# thermistory_array_v2.net
KiCad netlist of a schematic drawn in EAGLE
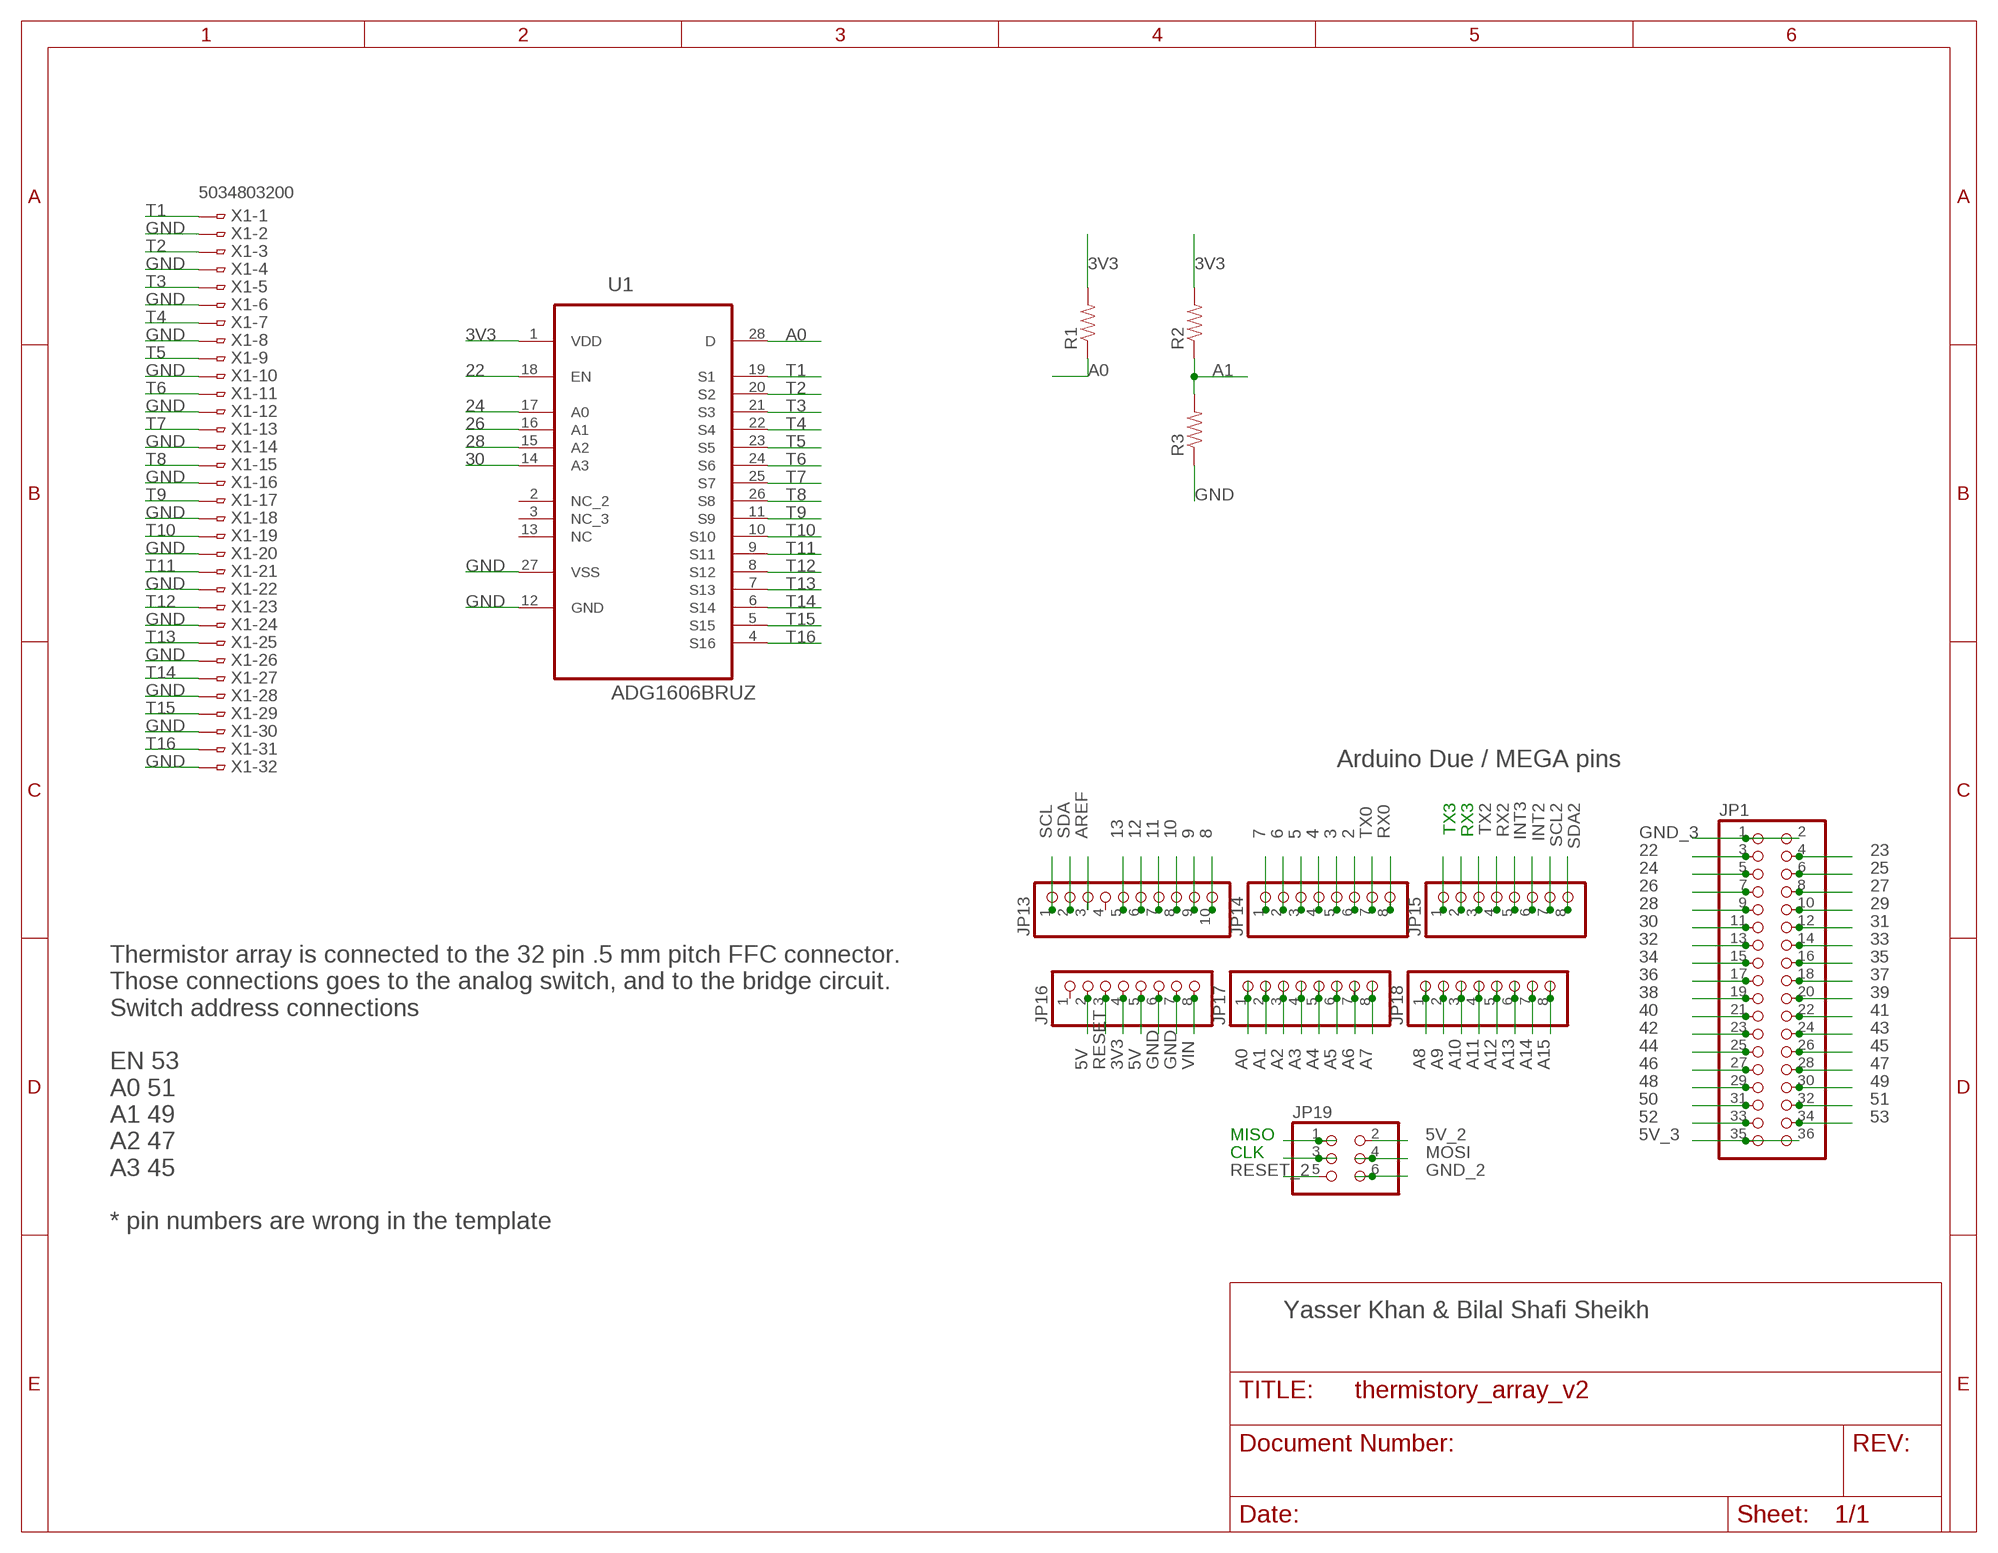
[diagram p0: schematic, sheet 1]

(export (version "E")
  (design (tool "Eeschema 10.0.6"))
  (components
    (comp (ref "JP1")
      (value "PINHD-2X18")
      (footprint "eagle-import:2X18")
      (libsource (lib "eagle-import") (part "PINHD-2X18"))
    )
    (comp (ref "JP13")
      (value "PINHD-1X10")
      (footprint "eagle-import:1X10")
      (libsource (lib "eagle-import") (part "PINHD-1X10"))
    )
    (comp (ref "JP14")
      (value "PINHD-1X8")
      (footprint "eagle-import:1X08")
      (libsource (lib "eagle-import") (part "PINHD-1X8"))
    )
    (comp (ref "JP15")
      (value "PINHD-1X8")
      (footprint "eagle-import:1X08")
      (libsource (lib "eagle-import") (part "PINHD-1X8"))
    )
    (comp (ref "JP16")
      (value "PINHD-1X8")
      (footprint "eagle-import:1X08")
      (libsource (lib "eagle-import") (part "PINHD-1X8"))
    )
    (comp (ref "JP17")
      (value "PINHD-1X8")
      (footprint "eagle-import:1X08")
      (libsource (lib "eagle-import") (part "PINHD-1X8"))
    )
    (comp (ref "JP18")
      (value "PINHD-1X8")
      (footprint "eagle-import:1X08")
      (libsource (lib "eagle-import") (part "PINHD-1X8"))
    )
    (comp (ref "JP19")
      (value "PINHD-2X3")
      (footprint "eagle-import:2X03")
      (libsource (lib "eagle-import") (part "PINHD-2X3"))
    )
    (comp (ref "R1")
      (value "RESISTORKIT")
      (footprint "eagle-import:AXIAL-0.3-KIT")
      (libsource (lib "eagle-import") (part "RESISTORKIT"))
    )
    (comp (ref "R2")
      (value "RESISTORKIT")
      (footprint "eagle-import:AXIAL-0.3-KIT")
      (libsource (lib "eagle-import") (part "RESISTORKIT"))
    )
    (comp (ref "R3")
      (value "RESISTORKIT")
      (footprint "eagle-import:AXIAL-0.3-KIT")
      (libsource (lib "eagle-import") (part "RESISTORKIT"))
    )
    (comp (ref "U1")
      (value "ADG1606BRUZ")
      (footprint "eagle-import:SOP65P640X120-28N")
      (libsource (lib "eagle-import") (part "ADG1606BRUZ"))
    )
    (comp (ref "X1")
      (value "5034803200")
      (footprint "eagle-import:5034803200")
      (libsource (lib "eagle-import") (part "5034803200"))
    )
  )
  (nets
    (net (code "1") (name "/2") (class "Default")
      (node (ref "JP14") (pin "6") (pinfunction "6_6") (pintype "passive"))
    )
    (net (code "2") (name "/3") (class "Default")
      (node (ref "JP14") (pin "5") (pinfunction "5_5") (pintype "passive"))
    )
    (net (code "3") (name "/3V3") (class "Default")
      (node (ref "JP16") (pin "4") (pinfunction "4_4") (pintype "passive"))
      (node (ref "R1") (pin "P$2") (pinfunction "2_P$2") (pintype "passive"))
      (node (ref "R2") (pin "P$2") (pinfunction "2_P$2") (pintype "passive"))
      (node (ref "U1") (pin "1") (pinfunction "VDD_1") (pintype "power_in"))
    )
    (net (code "4") (name "/4") (class "Default")
      (node (ref "JP14") (pin "4") (pinfunction "4_4") (pintype "passive"))
    )
    (net (code "5") (name "/5") (class "Default")
      (node (ref "JP14") (pin "3") (pinfunction "3_3") (pintype "passive"))
    )
    (net (code "6") (name "/5V") (class "Default")
      (node (ref "JP16") (pin "2") (pinfunction "2_2") (pintype "passive"))
      (node (ref "JP16") (pin "5") (pinfunction "5_5") (pintype "passive"))
    )
    (net (code "7") (name "/5V_2") (class "Default")
      (node (ref "JP19") (pin "2") (pinfunction "2_2") (pintype "passive"))
    )
    (net (code "8") (name "/5V_3") (class "Default")
      (node (ref "JP1") (pin "35") (pinfunction "35_35") (pintype "passive"))
      (node (ref "JP1") (pin "36") (pinfunction "36_36") (pintype "passive"))
    )
    (net (code "9") (name "/6") (class "Default")
      (node (ref "JP14") (pin "2") (pinfunction "2_2") (pintype "passive"))
    )
    (net (code "10") (name "/7") (class "Default")
      (node (ref "JP14") (pin "1") (pinfunction "1_1") (pintype "passive"))
    )
    (net (code "11") (name "/8") (class "Default")
      (node (ref "JP13") (pin "10") (pinfunction "10_10") (pintype "passive"))
    )
    (net (code "12") (name "/9") (class "Default")
      (node (ref "JP13") (pin "9") (pinfunction "9_9") (pintype "passive"))
    )
    (net (code "13") (name "/10") (class "Default")
      (node (ref "JP13") (pin "8") (pinfunction "8_8") (pintype "passive"))
    )
    (net (code "14") (name "/11") (class "Default")
      (node (ref "JP13") (pin "7") (pinfunction "7_7") (pintype "passive"))
    )
    (net (code "15") (name "/12") (class "Default")
      (node (ref "JP13") (pin "6") (pinfunction "6_6") (pintype "passive"))
    )
    (net (code "16") (name "/13") (class "Default")
      (node (ref "JP13") (pin "5") (pinfunction "5_5") (pintype "passive"))
    )
    (net (code "17") (name "/22") (class "Default")
      (node (ref "JP1") (pin "3") (pinfunction "3_3") (pintype "passive"))
      (node (ref "U1") (pin "18") (pinfunction "EN_18") (pintype "input"))
    )
    (net (code "18") (name "/23") (class "Default")
      (node (ref "JP1") (pin "4") (pinfunction "4_4") (pintype "passive"))
    )
    (net (code "19") (name "/24") (class "Default")
      (node (ref "JP1") (pin "5") (pinfunction "5_5") (pintype "passive"))
      (node (ref "U1") (pin "17") (pinfunction "A0_17") (pintype "input"))
    )
    (net (code "20") (name "/25") (class "Default")
      (node (ref "JP1") (pin "6") (pinfunction "6_6") (pintype "passive"))
    )
    (net (code "21") (name "/26") (class "Default")
      (node (ref "JP1") (pin "7") (pinfunction "7_7") (pintype "passive"))
      (node (ref "U1") (pin "16") (pinfunction "A1_16") (pintype "input"))
    )
    (net (code "22") (name "/27") (class "Default")
      (node (ref "JP1") (pin "8") (pinfunction "8_8") (pintype "passive"))
    )
    (net (code "23") (name "/28") (class "Default")
      (node (ref "JP1") (pin "9") (pinfunction "9_9") (pintype "passive"))
      (node (ref "U1") (pin "15") (pinfunction "A2_15") (pintype "input"))
    )
    (net (code "24") (name "/29") (class "Default")
      (node (ref "JP1") (pin "10") (pinfunction "10_10") (pintype "passive"))
    )
    (net (code "25") (name "/30") (class "Default")
      (node (ref "JP1") (pin "11") (pinfunction "11_11") (pintype "passive"))
      (node (ref "U1") (pin "14") (pinfunction "A3_14") (pintype "input"))
    )
    (net (code "26") (name "/31") (class "Default")
      (node (ref "JP1") (pin "12") (pinfunction "12_12") (pintype "passive"))
    )
    (net (code "27") (name "/32") (class "Default")
      (node (ref "JP1") (pin "13") (pinfunction "13_13") (pintype "passive"))
    )
    (net (code "28") (name "/33") (class "Default")
      (node (ref "JP1") (pin "14") (pinfunction "14_14") (pintype "passive"))
    )
    (net (code "29") (name "/34") (class "Default")
      (node (ref "JP1") (pin "15") (pinfunction "15_15") (pintype "passive"))
    )
    (net (code "30") (name "/35") (class "Default")
      (node (ref "JP1") (pin "16") (pinfunction "16_16") (pintype "passive"))
    )
    (net (code "31") (name "/36") (class "Default")
      (node (ref "JP1") (pin "17") (pinfunction "17_17") (pintype "passive"))
    )
    (net (code "32") (name "/37") (class "Default")
      (node (ref "JP1") (pin "18") (pinfunction "18_18") (pintype "passive"))
    )
    (net (code "33") (name "/38") (class "Default")
      (node (ref "JP1") (pin "19") (pinfunction "19_19") (pintype "passive"))
    )
    (net (code "34") (name "/39") (class "Default")
      (node (ref "JP1") (pin "20") (pinfunction "20_20") (pintype "passive"))
    )
    (net (code "35") (name "/40") (class "Default")
      (node (ref "JP1") (pin "21") (pinfunction "21_21") (pintype "passive"))
    )
    (net (code "36") (name "/41") (class "Default")
      (node (ref "JP1") (pin "22") (pinfunction "22_22") (pintype "passive"))
    )
    (net (code "37") (name "/42") (class "Default")
      (node (ref "JP1") (pin "23") (pinfunction "23_23") (pintype "passive"))
    )
    (net (code "38") (name "/43") (class "Default")
      (node (ref "JP1") (pin "24") (pinfunction "24_24") (pintype "passive"))
    )
    (net (code "39") (name "/44") (class "Default")
      (node (ref "JP1") (pin "25") (pinfunction "25_25") (pintype "passive"))
    )
    (net (code "40") (name "/45") (class "Default")
      (node (ref "JP1") (pin "26") (pinfunction "26_26") (pintype "passive"))
    )
    (net (code "41") (name "/46") (class "Default")
      (node (ref "JP1") (pin "27") (pinfunction "27_27") (pintype "passive"))
    )
    (net (code "42") (name "/47") (class "Default")
      (node (ref "JP1") (pin "28") (pinfunction "28_28") (pintype "passive"))
    )
    (net (code "43") (name "/48") (class "Default")
      (node (ref "JP1") (pin "29") (pinfunction "29_29") (pintype "passive"))
    )
    (net (code "44") (name "/49") (class "Default")
      (node (ref "JP1") (pin "30") (pinfunction "30_30") (pintype "passive"))
    )
    (net (code "45") (name "/50") (class "Default")
      (node (ref "JP1") (pin "31") (pinfunction "31_31") (pintype "passive"))
    )
    (net (code "46") (name "/51") (class "Default")
      (node (ref "JP1") (pin "32") (pinfunction "32_32") (pintype "passive"))
    )
    (net (code "47") (name "/52") (class "Default")
      (node (ref "JP1") (pin "33") (pinfunction "33_33") (pintype "passive"))
    )
    (net (code "48") (name "/53") (class "Default")
      (node (ref "JP1") (pin "34") (pinfunction "34_34") (pintype "passive"))
    )
    (net (code "49") (name "/A0") (class "Default")
      (node (ref "JP17") (pin "1") (pinfunction "1_1") (pintype "passive"))
      (node (ref "R1") (pin "P$1") (pinfunction "1_P$1") (pintype "passive"))
      (node (ref "U1") (pin "28") (pinfunction "D_28") (pintype "bidirectional"))
    )
    (net (code "50") (name "/A1") (class "Default")
      (node (ref "JP17") (pin "2") (pinfunction "2_2") (pintype "passive"))
      (node (ref "R2") (pin "P$1") (pinfunction "1_P$1") (pintype "passive"))
      (node (ref "R3") (pin "P$2") (pinfunction "2_P$2") (pintype "passive"))
    )
    (net (code "51") (name "/A2") (class "Default")
      (node (ref "JP17") (pin "3") (pinfunction "3_3") (pintype "passive"))
    )
    (net (code "52") (name "/A3") (class "Default")
      (node (ref "JP17") (pin "4") (pinfunction "4_4") (pintype "passive"))
    )
    (net (code "53") (name "/A4") (class "Default")
      (node (ref "JP17") (pin "5") (pinfunction "5_5") (pintype "passive"))
    )
    (net (code "54") (name "/A5") (class "Default")
      (node (ref "JP17") (pin "6") (pinfunction "6_6") (pintype "passive"))
    )
    (net (code "55") (name "/A6") (class "Default")
      (node (ref "JP17") (pin "7") (pinfunction "7_7") (pintype "passive"))
    )
    (net (code "56") (name "/A7") (class "Default")
      (node (ref "JP17") (pin "8") (pinfunction "8_8") (pintype "passive"))
    )
    (net (code "57") (name "/A8") (class "Default")
      (node (ref "JP18") (pin "1") (pinfunction "1_1") (pintype "passive"))
    )
    (net (code "58") (name "/A9") (class "Default")
      (node (ref "JP18") (pin "2") (pinfunction "2_2") (pintype "passive"))
    )
    (net (code "59") (name "/A10") (class "Default")
      (node (ref "JP18") (pin "3") (pinfunction "3_3") (pintype "passive"))
    )
    (net (code "60") (name "/A11") (class "Default")
      (node (ref "JP18") (pin "4") (pinfunction "4_4") (pintype "passive"))
    )
    (net (code "61") (name "/A12") (class "Default")
      (node (ref "JP18") (pin "5") (pinfunction "5_5") (pintype "passive"))
    )
    (net (code "62") (name "/A13") (class "Default")
      (node (ref "JP18") (pin "6") (pinfunction "6_6") (pintype "passive"))
    )
    (net (code "63") (name "/A14") (class "Default")
      (node (ref "JP18") (pin "7") (pinfunction "7_7") (pintype "passive"))
    )
    (net (code "64") (name "/A15") (class "Default")
      (node (ref "JP18") (pin "8") (pinfunction "8_8") (pintype "passive"))
    )
    (net (code "65") (name "/AREF") (class "Default")
      (node (ref "JP13") (pin "3") (pinfunction "3_3") (pintype "passive"))
    )
    (net (code "66") (name "/CLK") (class "Default")
      (node (ref "JP19") (pin "3") (pinfunction "3_3") (pintype "passive"))
    )
    (net (code "67") (name "/GND") (class "Default")
      (node (ref "JP16") (pin "6") (pinfunction "6_6") (pintype "passive"))
      (node (ref "JP16") (pin "7") (pinfunction "7_7") (pintype "passive"))
      (node (ref "R3") (pin "P$1") (pinfunction "1_P$1") (pintype "passive"))
      (node (ref "U1") (pin "12") (pinfunction "GND_12") (pintype "passive"))
      (node (ref "U1") (pin "27") (pinfunction "VSS_27") (pintype "power_in"))
      (node (ref "X1") (pin "10") (pinfunction "1_10") (pintype "passive"))
      (node (ref "X1") (pin "12") (pinfunction "1_12") (pintype "passive"))
      (node (ref "X1") (pin "14") (pinfunction "1_14") (pintype "passive"))
      (node (ref "X1") (pin "16") (pinfunction "1_16") (pintype "passive"))
      (node (ref "X1") (pin "18") (pinfunction "1_18") (pintype "passive"))
      (node (ref "X1") (pin "2") (pinfunction "1_2") (pintype "passive"))
      (node (ref "X1") (pin "20") (pinfunction "1_20") (pintype "passive"))
      (node (ref "X1") (pin "22") (pinfunction "1_22") (pintype "passive"))
      (node (ref "X1") (pin "24") (pinfunction "1_24") (pintype "passive"))
      (node (ref "X1") (pin "26") (pinfunction "1_26") (pintype "passive"))
      (node (ref "X1") (pin "28") (pinfunction "1_28") (pintype "passive"))
      (node (ref "X1") (pin "30") (pinfunction "1_30") (pintype "passive"))
      (node (ref "X1") (pin "32") (pinfunction "1_32") (pintype "passive"))
      (node (ref "X1") (pin "4") (pinfunction "1_4") (pintype "passive"))
      (node (ref "X1") (pin "6") (pinfunction "1_6") (pintype "passive"))
      (node (ref "X1") (pin "8") (pinfunction "1_8") (pintype "passive"))
    )
    (net (code "68") (name "/GND_2") (class "Default")
      (node (ref "JP19") (pin "6") (pinfunction "6_6") (pintype "passive"))
    )
    (net (code "69") (name "/GND_3") (class "Default")
      (node (ref "JP1") (pin "1") (pinfunction "1_1") (pintype "passive"))
      (node (ref "JP1") (pin "2") (pinfunction "2_2") (pintype "passive"))
    )
    (net (code "70") (name "/INT2") (class "Default")
      (node (ref "JP15") (pin "6") (pinfunction "6_6") (pintype "passive"))
    )
    (net (code "71") (name "/INT3") (class "Default")
      (node (ref "JP15") (pin "5") (pinfunction "5_5") (pintype "passive"))
    )
    (net (code "72") (name "/MISO") (class "Default")
      (node (ref "JP19") (pin "1") (pinfunction "1_1") (pintype "passive"))
    )
    (net (code "73") (name "/MOSI") (class "Default")
      (node (ref "JP19") (pin "4") (pinfunction "4_4") (pintype "passive"))
    )
    (net (code "74") (name "/RESET") (class "Default")
      (node (ref "JP16") (pin "3") (pinfunction "3_3") (pintype "passive"))
    )
    (net (code "75") (name "/RESET_2") (class "Default")
      (node (ref "JP19") (pin "5") (pinfunction "5_5") (pintype "passive"))
    )
    (net (code "76") (name "/RX0") (class "Default")
      (node (ref "JP14") (pin "8") (pinfunction "8_8") (pintype "passive"))
    )
    (net (code "77") (name "/RX2") (class "Default")
      (node (ref "JP15") (pin "4") (pinfunction "4_4") (pintype "passive"))
    )
    (net (code "78") (name "/RX3") (class "Default")
      (node (ref "JP15") (pin "2") (pinfunction "2_2") (pintype "passive"))
    )
    (net (code "79") (name "/SCL") (class "Default")
      (node (ref "JP13") (pin "1") (pinfunction "1_1") (pintype "passive"))
    )
    (net (code "80") (name "/SCL2") (class "Default")
      (node (ref "JP15") (pin "7") (pinfunction "7_7") (pintype "passive"))
    )
    (net (code "81") (name "/SDA") (class "Default")
      (node (ref "JP13") (pin "2") (pinfunction "2_2") (pintype "passive"))
    )
    (net (code "82") (name "/SDA2") (class "Default")
      (node (ref "JP15") (pin "8") (pinfunction "8_8") (pintype "passive"))
    )
    (net (code "83") (name "/T1") (class "Default")
      (node (ref "U1") (pin "19") (pinfunction "S1_19") (pintype "bidirectional"))
      (node (ref "X1") (pin "1") (pinfunction "1_1") (pintype "passive"))
    )
    (net (code "84") (name "/T2") (class "Default")
      (node (ref "U1") (pin "20") (pinfunction "S2_20") (pintype "bidirectional"))
      (node (ref "X1") (pin "3") (pinfunction "1_3") (pintype "passive"))
    )
    (net (code "85") (name "/T3") (class "Default")
      (node (ref "U1") (pin "21") (pinfunction "S3_21") (pintype "bidirectional"))
      (node (ref "X1") (pin "5") (pinfunction "1_5") (pintype "passive"))
    )
    (net (code "86") (name "/T4") (class "Default")
      (node (ref "U1") (pin "22") (pinfunction "S4_22") (pintype "bidirectional"))
      (node (ref "X1") (pin "7") (pinfunction "1_7") (pintype "passive"))
    )
    (net (code "87") (name "/T5") (class "Default")
      (node (ref "U1") (pin "23") (pinfunction "S5_23") (pintype "bidirectional"))
      (node (ref "X1") (pin "9") (pinfunction "1_9") (pintype "passive"))
    )
    (net (code "88") (name "/T6") (class "Default")
      (node (ref "U1") (pin "24") (pinfunction "S6_24") (pintype "bidirectional"))
      (node (ref "X1") (pin "11") (pinfunction "1_11") (pintype "passive"))
    )
    (net (code "89") (name "/T7") (class "Default")
      (node (ref "U1") (pin "25") (pinfunction "S7_25") (pintype "bidirectional"))
      (node (ref "X1") (pin "13") (pinfunction "1_13") (pintype "passive"))
    )
    (net (code "90") (name "/T8") (class "Default")
      (node (ref "U1") (pin "26") (pinfunction "S8_26") (pintype "bidirectional"))
      (node (ref "X1") (pin "15") (pinfunction "1_15") (pintype "passive"))
    )
    (net (code "91") (name "/T9") (class "Default")
      (node (ref "U1") (pin "11") (pinfunction "S9_11") (pintype "bidirectional"))
      (node (ref "X1") (pin "17") (pinfunction "1_17") (pintype "passive"))
    )
    (net (code "92") (name "/T10") (class "Default")
      (node (ref "U1") (pin "10") (pinfunction "S10_10") (pintype "bidirectional"))
      (node (ref "X1") (pin "19") (pinfunction "1_19") (pintype "passive"))
    )
    (net (code "93") (name "/T11") (class "Default")
      (node (ref "U1") (pin "9") (pinfunction "S11_9") (pintype "bidirectional"))
      (node (ref "X1") (pin "21") (pinfunction "1_21") (pintype "passive"))
    )
    (net (code "94") (name "/T12") (class "Default")
      (node (ref "U1") (pin "8") (pinfunction "S12_8") (pintype "bidirectional"))
      (node (ref "X1") (pin "23") (pinfunction "1_23") (pintype "passive"))
    )
    (net (code "95") (name "/T13") (class "Default")
      (node (ref "U1") (pin "7") (pinfunction "S13_7") (pintype "bidirectional"))
      (node (ref "X1") (pin "25") (pinfunction "1_25") (pintype "passive"))
    )
    (net (code "96") (name "/T14") (class "Default")
      (node (ref "U1") (pin "6") (pinfunction "S14_6") (pintype "bidirectional"))
      (node (ref "X1") (pin "27") (pinfunction "1_27") (pintype "passive"))
    )
    (net (code "97") (name "/T15") (class "Default")
      (node (ref "U1") (pin "5") (pinfunction "S15_5") (pintype "bidirectional"))
      (node (ref "X1") (pin "29") (pinfunction "1_29") (pintype "passive"))
    )
    (net (code "98") (name "/T16") (class "Default")
      (node (ref "U1") (pin "4") (pinfunction "S16_4") (pintype "bidirectional"))
      (node (ref "X1") (pin "31") (pinfunction "1_31") (pintype "passive"))
    )
    (net (code "99") (name "/TX0") (class "Default")
      (node (ref "JP14") (pin "7") (pinfunction "7_7") (pintype "passive"))
    )
    (net (code "100") (name "/TX2") (class "Default")
      (node (ref "JP15") (pin "3") (pinfunction "3_3") (pintype "passive"))
    )
    (net (code "101") (name "/TX3") (class "Default")
      (node (ref "JP15") (pin "1") (pinfunction "1_1") (pintype "passive"))
    )
    (net (code "102") (name "/VIN") (class "Default")
      (node (ref "JP16") (pin "8") (pinfunction "8_8") (pintype "passive"))
    )
    (net (code "103") (name "unconnected-(JP13-Pad4)") (class "Default")
      (node (ref "JP13") (pin "4") (pinfunction "4_4") (pintype "passive"))
    )
    (net (code "104") (name "unconnected-(JP16-Pad1)") (class "Default")
      (node (ref "JP16") (pin "1") (pinfunction "1_1") (pintype "passive"))
    )
    (net (code "105") (name "unconnected-(U1-NC-Pad13)") (class "Default")
      (node (ref "U1") (pin "13") (pinfunction "NC_13") (pintype "no_connect"))
    )
    (net (code "106") (name "unconnected-(U1-NC_2-Pad2)") (class "Default")
      (node (ref "U1") (pin "2") (pinfunction "NC_2_2") (pintype "no_connect"))
    )
    (net (code "107") (name "unconnected-(U1-NC_3-Pad3)") (class "Default")
      (node (ref "U1") (pin "3") (pinfunction "NC_3_3") (pintype "no_connect"))
    )
  )
)
